# 1_a_i_12_capacitance_schem.net
KiCad netlist of a schematic drawn in EAGLE
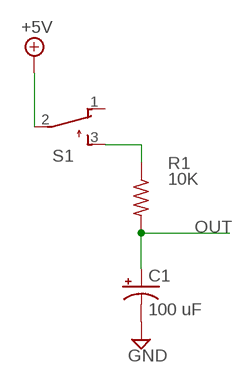
[diagram p0: schematic, sheet 1]

(export (version "E")
  (design (tool "Eeschema 10.0.6"))
  (components
    (comp (ref "C1")
      (value "100 uF")
      (footprint "eagle-import:B45181B")
      (libsource (lib "eagle-import") (part "CPOL-USB45181B"))
    )
    (comp (ref "R1")
      (value "10K")
      (footprint "eagle-import:0204_7")
      (libsource (lib "eagle-import") (part "R-US_0204/7"))
    )
    (comp (ref "S1")
      (value "TL32PO")
      (footprint "eagle-import:TL3XPO")
      (libsource (lib "eagle-import") (part "TL32PO"))
    )
  )
  (nets
    (net (code "1") (name "+5V") (class "Default")
      (node (ref "S1") (pin "2") (pinfunction "P_2") (pintype "passive"))
    )
    (net (code "2") (name "/OUT") (class "Default")
      (node (ref "C1") (pin "+") (pinfunction "+_+") (pintype "passive"))
      (node (ref "R1") (pin "2") (pinfunction "2_2") (pintype "passive"))
    )
    (net (code "3") (name "GND") (class "Default")
      (node (ref "C1") (pin "-") (pinfunction "-_-") (pintype "passive"))
    )
    (net (code "4") (name "Net-(S1-S)") (class "Default")
      (node (ref "R1") (pin "1") (pinfunction "1_1") (pintype "passive"))
      (node (ref "S1") (pin "3") (pinfunction "S_3") (pintype "passive"))
    )
    (net (code "5") (name "unconnected-(S1-O-Pad1)") (class "Default")
      (node (ref "S1") (pin "1") (pinfunction "O_1") (pintype "passive"))
    )
  )
)
